# ESP-3212_breakout_board.net
KiCad netlist of a schematic drawn in EAGLE
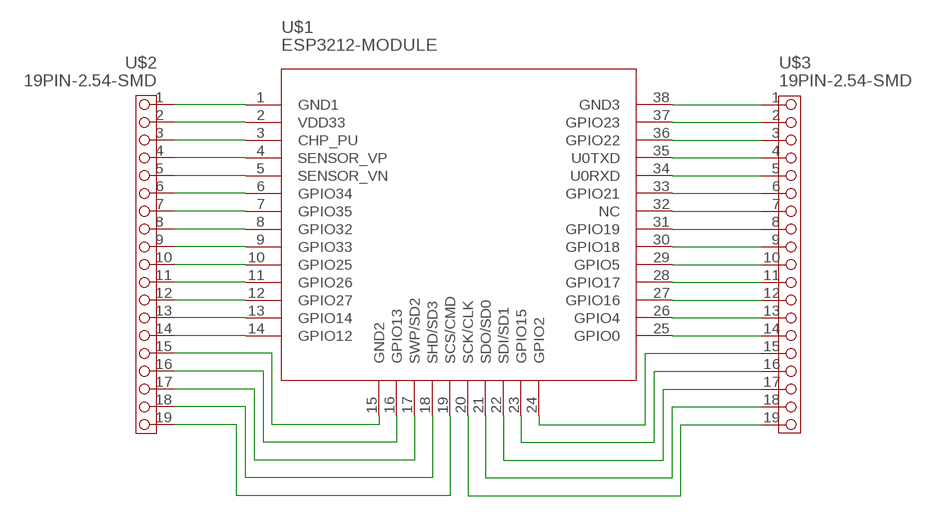
[diagram p0: schematic, sheet 1]

(export (version "E")
  (design (tool "Eeschema 10.0.6"))
  (components
    (comp (ref "U$1")
      (value "ESP3212-MODULE")
      (footprint "eagle-import:ESP3212-MODULE")
      (libsource (lib "eagle-import") (part "ESP3212-MODULE"))
    )
    (comp (ref "U$2")
      (value "19PIN-2.54-SMD")
      (footprint "eagle-import:19PIN-2.54-SMD")
      (libsource (lib "eagle-import") (part "19PIN-2.54-SMD"))
    )
    (comp (ref "U$3")
      (value "19PIN-2.54-SMD")
      (footprint "eagle-import:19PIN-2.54-SMD")
      (libsource (lib "eagle-import") (part "19PIN-2.54-SMD"))
    )
  )
  (nets
    (net (code "1") (name "/GND") (class "Default")
      (node (ref "U$1") (pin "1") (pinfunction "GND1_1") (pintype "bidirectional"))
      (node (ref "U$1") (pin "15") (pinfunction "GND2_15") (pintype "bidirectional"))
      (node (ref "U$1") (pin "38") (pinfunction "GND3_38") (pintype "bidirectional"))
      (node (ref "U$2") (pin "1") (pinfunction "1_1") (pintype "bidirectional"))
      (node (ref "U$2") (pin "15") (pinfunction "15_15") (pintype "bidirectional"))
      (node (ref "U$3") (pin "1") (pinfunction "1_1") (pintype "bidirectional"))
    )
    (net (code "2") (name "Net-(U$1-CHP_PU)") (class "Default")
      (node (ref "U$1") (pin "3") (pinfunction "CHP_PU_3") (pintype "bidirectional"))
      (node (ref "U$2") (pin "3") (pinfunction "3_3") (pintype "bidirectional"))
    )
    (net (code "3") (name "Net-(U$1-GPIO0)") (class "Default")
      (node (ref "U$1") (pin "25") (pinfunction "GPIO0_25") (pintype "bidirectional"))
      (node (ref "U$3") (pin "14") (pinfunction "14_14") (pintype "bidirectional"))
    )
    (net (code "4") (name "Net-(U$1-GPIO2)") (class "Default")
      (node (ref "U$1") (pin "24") (pinfunction "GPIO2_24") (pintype "bidirectional"))
      (node (ref "U$3") (pin "15") (pinfunction "15_15") (pintype "bidirectional"))
    )
    (net (code "5") (name "Net-(U$1-GPIO4)") (class "Default")
      (node (ref "U$1") (pin "26") (pinfunction "GPIO4_26") (pintype "bidirectional"))
      (node (ref "U$3") (pin "13") (pinfunction "13_13") (pintype "bidirectional"))
    )
    (net (code "6") (name "Net-(U$1-GPIO5)") (class "Default")
      (node (ref "U$1") (pin "29") (pinfunction "GPIO5_29") (pintype "bidirectional"))
      (node (ref "U$3") (pin "10") (pinfunction "10_10") (pintype "bidirectional"))
    )
    (net (code "7") (name "Net-(U$1-GPIO12)") (class "Default")
      (node (ref "U$1") (pin "14") (pinfunction "GPIO12_14") (pintype "bidirectional"))
      (node (ref "U$2") (pin "14") (pinfunction "14_14") (pintype "bidirectional"))
    )
    (net (code "8") (name "Net-(U$1-GPIO13)") (class "Default")
      (node (ref "U$1") (pin "16") (pinfunction "GPIO13_16") (pintype "bidirectional"))
      (node (ref "U$2") (pin "16") (pinfunction "16_16") (pintype "bidirectional"))
    )
    (net (code "9") (name "Net-(U$1-GPIO14)") (class "Default")
      (node (ref "U$1") (pin "13") (pinfunction "GPIO14_13") (pintype "bidirectional"))
      (node (ref "U$2") (pin "13") (pinfunction "13_13") (pintype "bidirectional"))
    )
    (net (code "10") (name "Net-(U$1-GPIO15)") (class "Default")
      (node (ref "U$1") (pin "23") (pinfunction "GPIO15_23") (pintype "bidirectional"))
      (node (ref "U$3") (pin "16") (pinfunction "16_16") (pintype "bidirectional"))
    )
    (net (code "11") (name "Net-(U$1-GPIO16)") (class "Default")
      (node (ref "U$1") (pin "27") (pinfunction "GPIO16_27") (pintype "bidirectional"))
      (node (ref "U$3") (pin "12") (pinfunction "12_12") (pintype "bidirectional"))
    )
    (net (code "12") (name "Net-(U$1-GPIO17)") (class "Default")
      (node (ref "U$1") (pin "28") (pinfunction "GPIO17_28") (pintype "bidirectional"))
      (node (ref "U$3") (pin "11") (pinfunction "11_11") (pintype "bidirectional"))
    )
    (net (code "13") (name "Net-(U$1-GPIO18)") (class "Default")
      (node (ref "U$1") (pin "30") (pinfunction "GPIO18_30") (pintype "bidirectional"))
      (node (ref "U$3") (pin "9") (pinfunction "9_9") (pintype "bidirectional"))
    )
    (net (code "14") (name "Net-(U$1-GPIO19)") (class "Default")
      (node (ref "U$1") (pin "31") (pinfunction "GPIO19_31") (pintype "bidirectional"))
      (node (ref "U$3") (pin "8") (pinfunction "8_8") (pintype "bidirectional"))
    )
    (net (code "15") (name "Net-(U$1-GPIO21)") (class "Default")
      (node (ref "U$1") (pin "33") (pinfunction "GPIO21_33") (pintype "bidirectional"))
      (node (ref "U$3") (pin "6") (pinfunction "6_6") (pintype "bidirectional"))
    )
    (net (code "16") (name "Net-(U$1-GPIO22)") (class "Default")
      (node (ref "U$1") (pin "36") (pinfunction "GPIO22_36") (pintype "bidirectional"))
      (node (ref "U$3") (pin "3") (pinfunction "3_3") (pintype "bidirectional"))
    )
    (net (code "17") (name "Net-(U$1-GPIO23)") (class "Default")
      (node (ref "U$1") (pin "37") (pinfunction "GPIO23_37") (pintype "bidirectional"))
      (node (ref "U$3") (pin "2") (pinfunction "2_2") (pintype "bidirectional"))
    )
    (net (code "18") (name "Net-(U$1-GPIO25)") (class "Default")
      (node (ref "U$1") (pin "10") (pinfunction "GPIO25_10") (pintype "bidirectional"))
      (node (ref "U$2") (pin "10") (pinfunction "10_10") (pintype "bidirectional"))
    )
    (net (code "19") (name "Net-(U$1-GPIO26)") (class "Default")
      (node (ref "U$1") (pin "11") (pinfunction "GPIO26_11") (pintype "bidirectional"))
      (node (ref "U$2") (pin "11") (pinfunction "11_11") (pintype "bidirectional"))
    )
    (net (code "20") (name "Net-(U$1-GPIO27)") (class "Default")
      (node (ref "U$1") (pin "12") (pinfunction "GPIO27_12") (pintype "bidirectional"))
      (node (ref "U$2") (pin "12") (pinfunction "12_12") (pintype "bidirectional"))
    )
    (net (code "21") (name "Net-(U$1-GPIO32)") (class "Default")
      (node (ref "U$1") (pin "8") (pinfunction "GPIO32_8") (pintype "bidirectional"))
      (node (ref "U$2") (pin "8") (pinfunction "8_8") (pintype "bidirectional"))
    )
    (net (code "22") (name "Net-(U$1-GPIO33)") (class "Default")
      (node (ref "U$1") (pin "9") (pinfunction "GPIO33_9") (pintype "bidirectional"))
      (node (ref "U$2") (pin "9") (pinfunction "9_9") (pintype "bidirectional"))
    )
    (net (code "23") (name "Net-(U$1-GPIO34)") (class "Default")
      (node (ref "U$1") (pin "6") (pinfunction "GPIO34_6") (pintype "bidirectional"))
      (node (ref "U$2") (pin "6") (pinfunction "6_6") (pintype "bidirectional"))
    )
    (net (code "24") (name "Net-(U$1-GPIO35)") (class "Default")
      (node (ref "U$1") (pin "7") (pinfunction "GPIO35_7") (pintype "bidirectional"))
      (node (ref "U$2") (pin "7") (pinfunction "7_7") (pintype "bidirectional"))
    )
    (net (code "25") (name "Net-(U$1-NC)") (class "Default")
      (node (ref "U$1") (pin "32") (pinfunction "NC_32") (pintype "bidirectional"))
      (node (ref "U$3") (pin "7") (pinfunction "7_7") (pintype "bidirectional"))
    )
    (net (code "26") (name "Net-(U$1-SCK{slash}CLK)") (class "Default")
      (node (ref "U$1") (pin "20") (pinfunction "SCK/CLK_20") (pintype "bidirectional"))
      (node (ref "U$3") (pin "19") (pinfunction "19_19") (pintype "bidirectional"))
    )
    (net (code "27") (name "Net-(U$1-SCS{slash}CMD)") (class "Default")
      (node (ref "U$1") (pin "19") (pinfunction "SCS/CMD_19") (pintype "bidirectional"))
      (node (ref "U$2") (pin "19") (pinfunction "19_19") (pintype "bidirectional"))
    )
    (net (code "28") (name "Net-(U$1-SDI{slash}SD1)") (class "Default")
      (node (ref "U$1") (pin "22") (pinfunction "SDI/SD1_22") (pintype "bidirectional"))
      (node (ref "U$3") (pin "17") (pinfunction "17_17") (pintype "bidirectional"))
    )
    (net (code "29") (name "Net-(U$1-SDO{slash}SD0)") (class "Default")
      (node (ref "U$1") (pin "21") (pinfunction "SDO/SD0_21") (pintype "bidirectional"))
      (node (ref "U$3") (pin "18") (pinfunction "18_18") (pintype "bidirectional"))
    )
    (net (code "30") (name "Net-(U$1-SENSOR_VN)") (class "Default")
      (node (ref "U$1") (pin "5") (pinfunction "SENSOR_VN_5") (pintype "bidirectional"))
      (node (ref "U$2") (pin "5") (pinfunction "5_5") (pintype "bidirectional"))
    )
    (net (code "31") (name "Net-(U$1-SENSOR_VP)") (class "Default")
      (node (ref "U$1") (pin "4") (pinfunction "SENSOR_VP_4") (pintype "bidirectional"))
      (node (ref "U$2") (pin "4") (pinfunction "4_4") (pintype "bidirectional"))
    )
    (net (code "32") (name "Net-(U$1-SHD{slash}SD3)") (class "Default")
      (node (ref "U$1") (pin "18") (pinfunction "SHD/SD3_18") (pintype "bidirectional"))
      (node (ref "U$2") (pin "18") (pinfunction "18_18") (pintype "bidirectional"))
    )
    (net (code "33") (name "Net-(U$1-SWP{slash}SD2)") (class "Default")
      (node (ref "U$1") (pin "17") (pinfunction "SWP/SD2_17") (pintype "bidirectional"))
      (node (ref "U$2") (pin "17") (pinfunction "17_17") (pintype "bidirectional"))
    )
    (net (code "34") (name "Net-(U$1-U0RXD)") (class "Default")
      (node (ref "U$1") (pin "34") (pinfunction "U0RXD_34") (pintype "bidirectional"))
      (node (ref "U$3") (pin "5") (pinfunction "5_5") (pintype "bidirectional"))
    )
    (net (code "35") (name "Net-(U$1-U0TXD)") (class "Default")
      (node (ref "U$1") (pin "35") (pinfunction "U0TXD_35") (pintype "bidirectional"))
      (node (ref "U$3") (pin "4") (pinfunction "4_4") (pintype "bidirectional"))
    )
    (net (code "36") (name "Net-(U$1-VDD33)") (class "Default")
      (node (ref "U$1") (pin "2") (pinfunction "VDD33_2") (pintype "bidirectional"))
      (node (ref "U$2") (pin "2") (pinfunction "2_2") (pintype "bidirectional"))
    )
  )
)
